# working.net
KiCad netlist of a schematic drawn in EAGLE
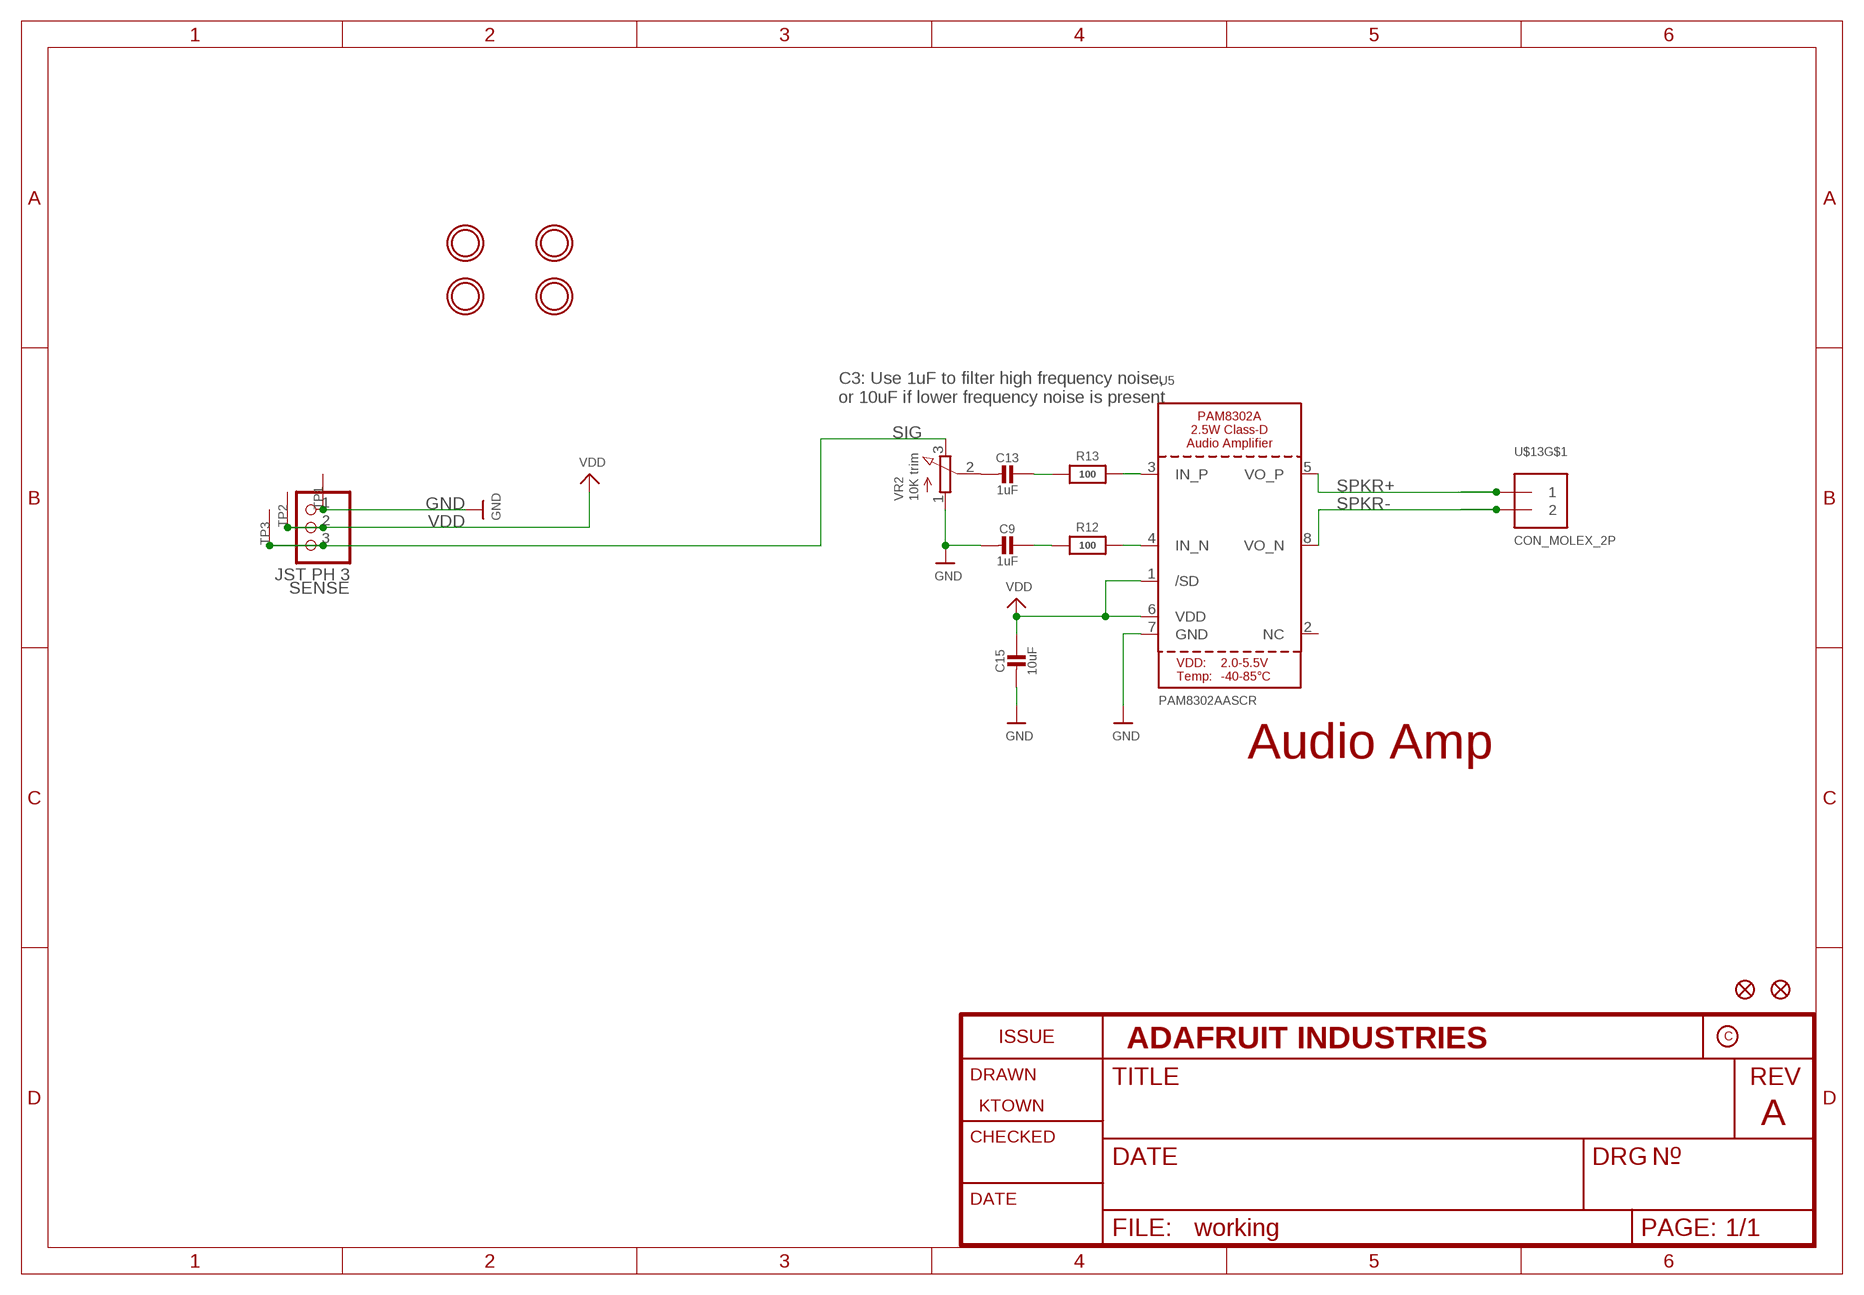
[diagram p0: schematic, sheet 1]

(export (version "E")
  (design (tool "Eeschema 10.0.6"))
  (components
    (comp (ref "C9")
      (value "1uF")
      (footprint "eagle-import:0603-NO")
      (libsource (lib "eagle-import") (part "CAP_CERAMIC0603_NO"))
    )
    (comp (ref "C13")
      (value "1uF")
      (footprint "eagle-import:0603-NO")
      (libsource (lib "eagle-import") (part "CAP_CERAMIC0603_NO"))
    )
    (comp (ref "C15")
      (value "10uF")
      (footprint "eagle-import:0805-NO")
      (libsource (lib "eagle-import") (part "CAP_CERAMIC0805-NOOUTLINE"))
    )
    (comp (ref "FID1")
      (value "FIDUCIAL_1MM")
      (footprint "eagle-import:FIDUCIAL_1MM")
      (libsource (lib "eagle-import") (part "FIDUCIAL_1MM"))
    )
    (comp (ref "FID2")
      (value "FIDUCIAL_1MM")
      (footprint "eagle-import:FIDUCIAL_1MM")
      (libsource (lib "eagle-import") (part "FIDUCIAL_1MM"))
    )
    (comp (ref "R12")
      (value "100")
      (footprint "eagle-import:0603-NO")
      (libsource (lib "eagle-import") (part "RESISTOR_0603_NOOUT"))
    )
    (comp (ref "R13")
      (value "100")
      (footprint "eagle-import:0603-NO")
      (libsource (lib "eagle-import") (part "RESISTOR_0603_NOOUT"))
    )
    (comp (ref "SENSE")
      (value "JST PH 3")
      (footprint "eagle-import:JSTPH3")
      (libsource (lib "eagle-import") (part "CON_JST_PH_3PIN"))
    )
    (comp (ref "TP1")
      (value "SEWTAPPCB_ALLIGATOR")
      (footprint "eagle-import:PCB_ALLI")
      (libsource (lib "eagle-import") (part "SEWTAPPCB_ALLIGATOR"))
    )
    (comp (ref "TP2")
      (value "SEWTAPPCB_ALLIGATOR")
      (footprint "eagle-import:PCB_ALLI")
      (libsource (lib "eagle-import") (part "SEWTAPPCB_ALLIGATOR"))
    )
    (comp (ref "TP3")
      (value "SEWTAPPCB_ALLIGATOR")
      (footprint "eagle-import:PCB_ALLI")
      (libsource (lib "eagle-import") (part "SEWTAPPCB_ALLIGATOR"))
    )
    (comp (ref "U$9")
      (value "MOUNTINGHOLE2.0")
      (footprint "eagle-import:MOUNTINGHOLE_2.0_PLATED")
      (libsource (lib "eagle-import") (part "MOUNTINGHOLE2.0"))
    )
    (comp (ref "U$10")
      (value "MOUNTINGHOLE2.0")
      (footprint "eagle-import:MOUNTINGHOLE_2.0_PLATED")
      (libsource (lib "eagle-import") (part "MOUNTINGHOLE2.0"))
    )
    (comp (ref "U$11")
      (value "MOUNTINGHOLE2.0")
      (footprint "eagle-import:MOUNTINGHOLE_2.0_PLATED")
      (libsource (lib "eagle-import") (part "MOUNTINGHOLE2.0"))
    )
    (comp (ref "U$12")
      (value "MOUNTINGHOLE2.0")
      (footprint "eagle-import:MOUNTINGHOLE_2.0_PLATED")
      (libsource (lib "eagle-import") (part "MOUNTINGHOLE2.0"))
    )
    (comp (ref "U$13")
      (value "CON_MOLEX_2P")
      (footprint "eagle-import:53398-0271")
      (libsource (lib "eagle-import") (part "CON_MOLEX_2P"))
    )
    (comp (ref "U5")
      (value "PAM8302AASCR")
      (footprint "eagle-import:MSOP8_0.65MM")
      (libsource (lib "eagle-import") (part "AUDIOAMP_PAM8302A"))
    )
    (comp (ref "VR2")
      (value "10K trim")
      (footprint "eagle-import:TRIMPOT_BOURNS_3303W")
      (libsource (lib "eagle-import") (part "TRIMPOT3303W/X"))
    )
  )
  (nets
    (net (code "1") (name "/SIG") (class "Default")
      (node (ref "SENSE") (pin "3") (pinfunction "3_3") (pintype "passive"))
      (node (ref "TP3") (pin "P$1") (pinfunction "SEW_P$1") (pintype "bidirectional"))
      (node (ref "VR2") (pin "3") (pinfunction "E_3") (pintype "passive"))
    )
    (net (code "2") (name "/SPKR+") (class "Default")
      (node (ref "U$13") (pin "1") (pinfunction "1_1") (pintype "passive"))
      (node (ref "U5") (pin "5") (pinfunction "VO_P_5") (pintype "output"))
    )
    (net (code "3") (name "/SPKR-") (class "Default")
      (node (ref "U$13") (pin "2") (pinfunction "2_2") (pintype "passive"))
      (node (ref "U5") (pin "8") (pinfunction "VO_N_8") (pintype "output"))
    )
    (net (code "4") (name "GND") (class "Default")
      (node (ref "C15") (pin "2") (pinfunction "2_2") (pintype "passive"))
      (node (ref "C9") (pin "2") (pinfunction "2_2") (pintype "passive"))
      (node (ref "SENSE") (pin "1") (pinfunction "1_1") (pintype "passive"))
      (node (ref "TP1") (pin "P$1") (pinfunction "SEW_P$1") (pintype "bidirectional"))
      (node (ref "U5") (pin "7") (pinfunction "GND_7") (pintype "power_in"))
      (node (ref "VR2") (pin "1") (pinfunction "A_1") (pintype "passive"))
    )
    (net (code "5") (name "Net-(C9-Pad1)") (class "Default")
      (node (ref "C9") (pin "1") (pinfunction "1_1") (pintype "passive"))
      (node (ref "R12") (pin "1") (pinfunction "1_1") (pintype "passive"))
    )
    (net (code "6") (name "Net-(C13-Pad1)") (class "Default")
      (node (ref "C13") (pin "1") (pinfunction "1_1") (pintype "passive"))
      (node (ref "R13") (pin "1") (pinfunction "1_1") (pintype "passive"))
    )
    (net (code "7") (name "Net-(U5-IN_N)") (class "Default")
      (node (ref "R12") (pin "2") (pinfunction "2_2") (pintype "passive"))
      (node (ref "U5") (pin "4") (pinfunction "IN_N_4") (pintype "input"))
    )
    (net (code "8") (name "Net-(U5-IN_P)") (class "Default")
      (node (ref "R13") (pin "2") (pinfunction "2_2") (pintype "passive"))
      (node (ref "U5") (pin "3") (pinfunction "IN_P_3") (pintype "input"))
    )
    (net (code "9") (name "Net-(VR2-S)") (class "Default")
      (node (ref "C13") (pin "2") (pinfunction "2_2") (pintype "passive"))
      (node (ref "VR2") (pin "2") (pinfunction "S_2") (pintype "passive"))
    )
    (net (code "10") (name "VDD") (class "Default")
      (node (ref "C15") (pin "1") (pinfunction "1_1") (pintype "passive"))
      (node (ref "SENSE") (pin "2") (pinfunction "2_2") (pintype "passive"))
      (node (ref "TP2") (pin "P$1") (pinfunction "SEW_P$1") (pintype "bidirectional"))
      (node (ref "U5") (pin "1") (pinfunction "/SD_1") (pintype "input"))
      (node (ref "U5") (pin "6") (pinfunction "VDD_6") (pintype "power_in"))
    )
    (net (code "11") (name "unconnected-(U5-NC-Pad2)") (class "Default")
      (node (ref "U5") (pin "2") (pinfunction "NC_2") (pintype "no_connect"))
    )
  )
)
